# Nixie_Design_Block.net
KiCad netlist of a schematic drawn in EAGLE
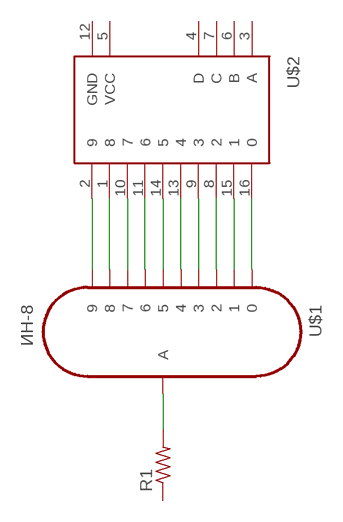
[diagram p0: schematic, sheet 1]

(export (version "E")
  (design (tool "Eeschema 10.0.6"))
  (components
    (comp (ref "R1")
      (value "R-US_M0805")
      (footprint "eagle-import:M0805")
      (libsource (lib "eagle-import") (part "R-US_M0805"))
    )
    (comp (ref "U$1")
      (value "ИН-8")
      (footprint "eagle-import:IN-8_SOCKET")
      (libsource (lib "eagle-import") (part "IN-8IN-8_SOCKET"))
    )
    (comp (ref "U$2")
      (value "K155ID1")
      (footprint "eagle-import:DIL16-KIT")
      (libsource (lib "eagle-import") (part "K155ID1"))
    )
  )
  (nets
    (net (code "1") (name "Net-(R1-Pad2)") (class "Default")
      (node (ref "R1") (pin "2") (pinfunction "2_2") (pintype "passive"))
      (node (ref "U$1") (pin "A") (pinfunction "A_A") (pintype "bidirectional"))
    )
    (net (code "2") (name "Net-(U$2-0)") (class "Default")
      (node (ref "U$1") (pin "0") (pinfunction "0_0") (pintype "bidirectional"))
      (node (ref "U$2") (pin "16") (pinfunction "0_16") (pintype "bidirectional"))
    )
    (net (code "3") (name "Net-(U$2-1)") (class "Default")
      (node (ref "U$1") (pin "1") (pinfunction "1_1") (pintype "bidirectional"))
      (node (ref "U$2") (pin "15") (pinfunction "1_15") (pintype "bidirectional"))
    )
    (net (code "4") (name "Net-(U$2-2)") (class "Default")
      (node (ref "U$1") (pin "2") (pinfunction "2_2") (pintype "bidirectional"))
      (node (ref "U$2") (pin "8") (pinfunction "2_8") (pintype "bidirectional"))
    )
    (net (code "5") (name "Net-(U$2-3)") (class "Default")
      (node (ref "U$1") (pin "3") (pinfunction "3_3") (pintype "bidirectional"))
      (node (ref "U$2") (pin "9") (pinfunction "3_9") (pintype "bidirectional"))
    )
    (net (code "6") (name "Net-(U$2-4)") (class "Default")
      (node (ref "U$1") (pin "4") (pinfunction "4_4") (pintype "bidirectional"))
      (node (ref "U$2") (pin "13") (pinfunction "4_13") (pintype "bidirectional"))
    )
    (net (code "7") (name "Net-(U$2-5)") (class "Default")
      (node (ref "U$1") (pin "5") (pinfunction "5_5") (pintype "bidirectional"))
      (node (ref "U$2") (pin "14") (pinfunction "5_14") (pintype "bidirectional"))
    )
    (net (code "8") (name "Net-(U$2-6)") (class "Default")
      (node (ref "U$1") (pin "6") (pinfunction "6_6") (pintype "bidirectional"))
      (node (ref "U$2") (pin "11") (pinfunction "6_11") (pintype "bidirectional"))
    )
    (net (code "9") (name "Net-(U$2-7)") (class "Default")
      (node (ref "U$1") (pin "7") (pinfunction "7_7") (pintype "bidirectional"))
      (node (ref "U$2") (pin "10") (pinfunction "7_10") (pintype "bidirectional"))
    )
    (net (code "10") (name "Net-(U$2-8)") (class "Default")
      (node (ref "U$1") (pin "8") (pinfunction "8_8") (pintype "bidirectional"))
      (node (ref "U$2") (pin "1") (pinfunction "8_1") (pintype "bidirectional"))
    )
    (net (code "11") (name "Net-(U$2-9)") (class "Default")
      (node (ref "U$1") (pin "9") (pinfunction "9_9") (pintype "bidirectional"))
      (node (ref "U$2") (pin "2") (pinfunction "9_2") (pintype "bidirectional"))
    )
    (net (code "12") (name "unconnected-(R1-Pad1)") (class "Default")
      (node (ref "R1") (pin "1") (pinfunction "1_1") (pintype "passive"))
    )
    (net (code "13") (name "unconnected-(U$2-A-Pad3)") (class "Default")
      (node (ref "U$2") (pin "3") (pinfunction "A_3") (pintype "input"))
    )
    (net (code "14") (name "unconnected-(U$2-B-Pad6)") (class "Default")
      (node (ref "U$2") (pin "6") (pinfunction "B_6") (pintype "input"))
    )
    (net (code "15") (name "unconnected-(U$2-C-Pad7)") (class "Default")
      (node (ref "U$2") (pin "7") (pinfunction "C_7") (pintype "input"))
    )
    (net (code "16") (name "unconnected-(U$2-D-Pad4)") (class "Default")
      (node (ref "U$2") (pin "4") (pinfunction "D_4") (pintype "input"))
    )
    (net (code "17") (name "unconnected-(U$2-GND-Pad12)") (class "Default")
      (node (ref "U$2") (pin "12") (pinfunction "GND_12") (pintype "bidirectional"))
    )
    (net (code "18") (name "unconnected-(U$2-VCC-Pad5)") (class "Default")
      (node (ref "U$2") (pin "5") (pinfunction "VCC_5") (pintype "bidirectional"))
    )
  )
)
